# BMS.net
KiCad netlist of a schematic drawn in Altium Designer
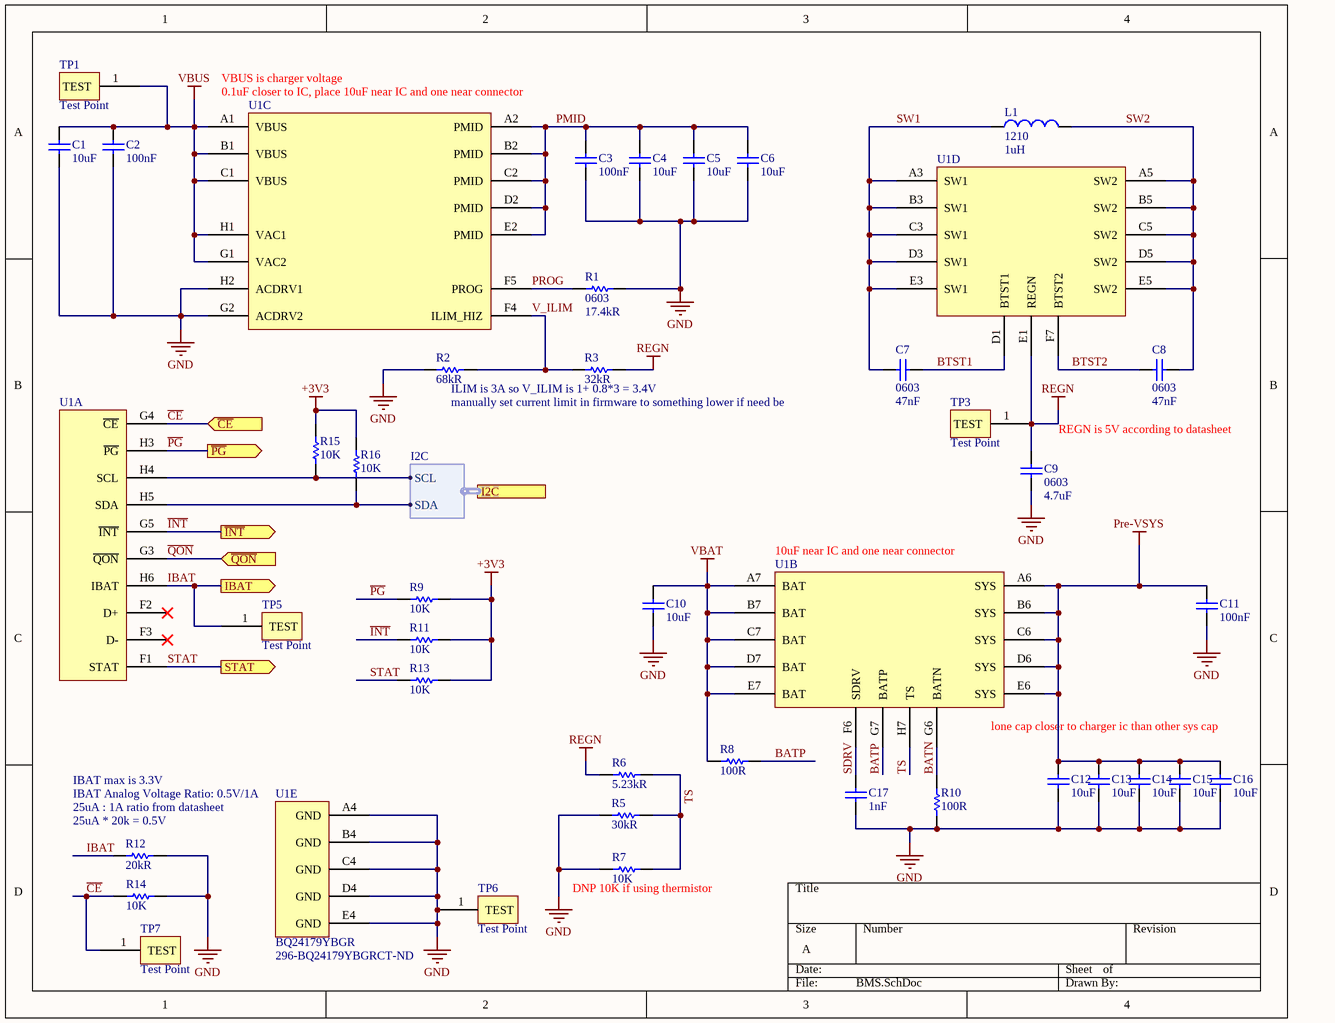
[diagram p0: BMS.SchDoc]

(export (version "E")
  (design (tool "Eeschema 10.0.6"))
  (components
    (comp (ref "C1")
      (value "Capacitor 0603")
      (footprint "C0603")
      (description "Multilayer Ceramic Capacitors (High dielectric type), 25V, 10 uF, ± 20 %, 0603, X5R, RoHS")
      (fields
        (field (name "MANUFACTURER") "Taiyo Yuden")
        (field (name "MANUFACTURER PART NUMBER") "TMK107BBJ106MA-T")
        (field (name "CAPACITANCE") "10uF")
      )
      (libsource (lib "Wally_BMS") (part "Capacitor 0603"))
    )
    (comp (ref "C2")
      (value "Capacitor 0402")
      (footprint "C0402")
      (description "CAP CER 0.1UF 25V X5R 0402 / High Value Multilayer Ceramic Capacitors (High dielectric type)")
      (fields
        (field (name "MANUFACTURER") "Taiyo Yuden")
        (field (name "MANUFACTURER PART NUMBER") "TMK105BJ104KV-F")
        (field (name "CAPACITANCE") "100nF")
      )
      (libsource (lib "Wally_BMS") (part "Capacitor 0402"))
    )
    (comp (ref "C3")
      (value "Capacitor 0402")
      (footprint "C0402")
      (description "CAP CER 0.1UF 25V X5R 0402 / High Value Multilayer Ceramic Capacitors (High dielectric type)")
      (fields
        (field (name "MANUFACTURER") "Taiyo Yuden")
        (field (name "MANUFACTURER PART NUMBER") "TMK105BJ104KV-F")
        (field (name "CAPACITANCE") "100nF")
      )
      (libsource (lib "Wally_BMS") (part "Capacitor 0402"))
    )
    (comp (ref "C4")
      (value "Capacitor 0603")
      (footprint "C0603")
      (description "Multilayer Ceramic Capacitors (High dielectric type), 25V, 10 uF, ± 20 %, 0603, X5R, RoHS")
      (fields
        (field (name "MANUFACTURER") "Taiyo Yuden")
        (field (name "MANUFACTURER PART NUMBER") "TMK107BBJ106MA-T")
        (field (name "CAPACITANCE") "10uF")
      )
      (libsource (lib "Wally_BMS") (part "Capacitor 0603"))
    )
    (comp (ref "C5")
      (value "Capacitor 0603")
      (footprint "C0603")
      (description "Multilayer Ceramic Capacitors (High dielectric type), 25V, 10 uF, ± 20 %, 0603, X5R, RoHS")
      (fields
        (field (name "MANUFACTURER") "Taiyo Yuden")
        (field (name "MANUFACTURER PART NUMBER") "TMK107BBJ106MA-T")
        (field (name "CAPACITANCE") "10uF")
      )
      (libsource (lib "Wally_BMS") (part "Capacitor 0603"))
    )
    (comp (ref "C6")
      (value "Capacitor 0603")
      (footprint "C0603")
      (description "Multilayer Ceramic Capacitors (High dielectric type), 25V, 10 uF, ± 20 %, 0603, X5R, RoHS")
      (fields
        (field (name "MANUFACTURER") "Taiyo Yuden")
        (field (name "MANUFACTURER PART NUMBER") "TMK107BBJ106MA-T")
        (field (name "CAPACITANCE") "10uF")
      )
      (libsource (lib "Wally_BMS") (part "Capacitor 0603"))
    )
    (comp (ref "C7")
      (value "Capacitor 0603")
      (footprint "C0603")
      (description "Cap Ceramic 0.047uF 50V X7R 10% SMD 0603 125°C Paper T/R")
      (fields
        (field (name "PACKAGE / CASE") "0603")
        (field (name "MANUFACTURER") "KEMET")
        (field (name "MANUFACTURER PART NUMBER") "C0603C473K5RAC7411")
        (field (name "CAPACITANCE") "47nF")
      )
      (libsource (lib "Wally_BMS") (part "Capacitor 0603"))
    )
    (comp (ref "C8")
      (value "Capacitor 0603")
      (footprint "C0603")
      (description "Cap Ceramic 0.047uF 50V X7R 10% SMD 0603 125°C Paper T/R")
      (fields
        (field (name "PACKAGE / CASE") "0603")
        (field (name "MANUFACTURER") "KEMET")
        (field (name "MANUFACTURER PART NUMBER") "C0603C473K5RAC7411")
        (field (name "CAPACITANCE") "47nF")
      )
      (libsource (lib "Wally_BMS") (part "Capacitor 0603"))
    )
    (comp (ref "C9")
      (value "Capacitor 0603")
      (footprint "C0603")
      (description "CAP CER 4.7UF 25V X5R 0603")
      (fields
        (field (name "PACKAGE / CASE") "0603")
        (field (name "MANUFACTURER") "TDK")
        (field (name "MANUFACTURER PART NUMBER") "C1608X5R1E475M080AC")
        (field (name "CAPACITANCE") "4.7uF")
      )
      (libsource (lib "Wally_BMS") (part "Capacitor 0603"))
    )
    (comp (ref "C10")
      (value "Capacitor 0603")
      (footprint "C0603")
      (description "Multilayer Ceramic Capacitors (High dielectric type), 25V, 10 uF, ± 20 %, 0603, X5R, RoHS")
      (fields
        (field (name "MANUFACTURER") "Taiyo Yuden")
        (field (name "MANUFACTURER PART NUMBER") "TMK107BBJ106MA-T")
        (field (name "CAPACITANCE") "10uF")
      )
      (libsource (lib "Wally_BMS") (part "Capacitor 0603"))
    )
    (comp (ref "C11")
      (value "Capacitor 0402")
      (footprint "C0402")
      (description "CAP CER 0.1UF 25V X5R 0402 / High Value Multilayer Ceramic Capacitors (High dielectric type)")
      (fields
        (field (name "MANUFACTURER") "Taiyo Yuden")
        (field (name "MANUFACTURER PART NUMBER") "TMK105BJ104KV-F")
        (field (name "CAPACITANCE") "100nF")
      )
      (libsource (lib "Wally_BMS") (part "Capacitor 0402"))
    )
    (comp (ref "C12")
      (value "Capacitor 0603")
      (footprint "C0603")
      (description "Multilayer Ceramic Capacitors (High dielectric type), 25V, 10 uF, ± 20 %, 0603, X5R, RoHS")
      (fields
        (field (name "MANUFACTURER") "Taiyo Yuden")
        (field (name "MANUFACTURER PART NUMBER") "TMK107BBJ106MA-T")
        (field (name "CAPACITANCE") "10uF")
      )
      (libsource (lib "Wally_BMS") (part "Capacitor 0603"))
    )
    (comp (ref "C13")
      (value "Capacitor 0603")
      (footprint "C0603")
      (description "Multilayer Ceramic Capacitors (High dielectric type), 25V, 10 uF, ± 20 %, 0603, X5R, RoHS")
      (fields
        (field (name "MANUFACTURER") "Taiyo Yuden")
        (field (name "MANUFACTURER PART NUMBER") "TMK107BBJ106MA-T")
        (field (name "CAPACITANCE") "10uF")
      )
      (libsource (lib "Wally_BMS") (part "Capacitor 0603"))
    )
    (comp (ref "C14")
      (value "Capacitor 0603")
      (footprint "C0603")
      (description "Multilayer Ceramic Capacitors (High dielectric type), 25V, 10 uF, ± 20 %, 0603, X5R, RoHS")
      (fields
        (field (name "MANUFACTURER") "Taiyo Yuden")
        (field (name "MANUFACTURER PART NUMBER") "TMK107BBJ106MA-T")
        (field (name "CAPACITANCE") "10uF")
      )
      (libsource (lib "Wally_BMS") (part "Capacitor 0603"))
    )
    (comp (ref "C15")
      (value "Capacitor 0603")
      (footprint "C0603")
      (description "Multilayer Ceramic Capacitors (High dielectric type), 25V, 10 uF, ± 20 %, 0603, X5R, RoHS")
      (fields
        (field (name "MANUFACTURER") "Taiyo Yuden")
        (field (name "MANUFACTURER PART NUMBER") "TMK107BBJ106MA-T")
        (field (name "CAPACITANCE") "10uF")
      )
      (libsource (lib "Wally_BMS") (part "Capacitor 0603"))
    )
    (comp (ref "C16")
      (value "Capacitor 0603")
      (footprint "C0603")
      (description "Multilayer Ceramic Capacitors (High dielectric type), 25V, 10 uF, ± 20 %, 0603, X5R, RoHS")
      (fields
        (field (name "MANUFACTURER") "Taiyo Yuden")
        (field (name "MANUFACTURER PART NUMBER") "TMK107BBJ106MA-T")
        (field (name "CAPACITANCE") "10uF")
      )
      (libsource (lib "Wally_BMS") (part "Capacitor 0603"))
    )
    (comp (ref "C17")
      (value "478-1215-1-ND")
      (footprint "C0603")
      (description "CAP CER 1000PF 50V X7R 0603")
      (fields (field (name "TOLERANCE") "±20%") (field (name "CAPACITANCE") "1nF"))
      (libsource (lib "Capacitors") (part "06035C102KAT2A"))
    )
    (comp (ref "L1")
      (value "Inductor 1210")
      (footprint "ind1210")
      (description "Inductor Power Shielded Wirewound 1uH 20% 1MHz Metal 4.1A 0.022Ohm DCR 1210 Automotive T/R")
      (fields
        (field (name "PACKAGE / CASE") "1210")
        (field (name "MANUFACTURER") "Murata")
        (field (name "MANUFACTURER PART NUMBER") "DFE322520FD-1R0M=P2")
        (field (name "INDUCTANCE") "1uH")
      )
      (libsource (lib "Wally_BMS") (part "Inductor 1210"))
    )
    (comp (ref "R1")
      (value "Resistor 0603")
      (footprint "RES0603")
      (description "Res Thick Film 0603 17.4K Ohm 1% 0.1W(1/10W) ±100ppm/°C Pad SMD Automotive T/R")
      (fields
        (field (name "PACKAGE / CASE") "0603")
        (field (name "MANUFACTURER") "Stackpole Electronics")
        (field (name "MANUFACTURER PART NUMBER") "RMCF0603FT17K4")
        (field (name "RESISTANCE") "17.4kR")
      )
      (libsource (lib "Wally_BMS") (part "Resistor 0603"))
    )
    (comp (ref "R2")
      (value "Resistor 0402")
      (footprint "RES0402")
      (description "Res Thin Film 0402 68K Ohm 0.1% 0.063W ±25ppm/°C Molded SMD Punched Carrier T/R")
      (fields
        (field (name "MANUFACTURER") "Panasonic")
        (field (name "MANUFACTURER PART NUMBER") "ERA-2AEB683X")
        (field (name "RESISTANCE") "68kR")
      )
      (libsource (lib "Wally_BMS") (part "Resistor 0402"))
    )
    (comp (ref "R3")
      (value "Resistor 0402")
      (footprint "RES0402")
      (description "Res, 32K, 1%, 0.063W, 0402 Rohs Compliant: Yes")
      (fields
        (field (name "MANUFACTURER") "KOA Speer")
        (field (name "MANUFACTURER PART NUMBER") "RN73H1ETTP3202F50")
        (field (name "RESISTANCE") "32kR")
      )
      (libsource (lib "Wally_BMS") (part "Resistor 0402"))
    )
    (comp (ref "R5")
      (value "Resistor 0402")
      (footprint "RES0402")
      (description "Res Thick Film 0402 30K Ohm 5% 0.063W(1/16W) ±100ppm/C Pad SMD Automotive T/R")
      (fields
        (field (name "MANUFACTURER") "Stackpole Electronics")
        (field (name "MANUFACTURER PART NUMBER") "RMCF0402JT30K0")
        (field (name "RESISTANCE") "30kR")
      )
      (libsource (lib "Wally_BMS") (part "Resistor 0402"))
    )
    (comp (ref "R6")
      (value "Resistor 0402")
      (footprint "RES0402")
      (description "Res Thick Film 0402 5.23K Ohm 1% 0.063W ±100ppm/°C Molded SMD Paper T/R")
      (fields
        (field (name "MANUFACTURER") "Stackpole Electronics")
        (field (name "MANUFACTURER PART NUMBER") "RMCF0402FT5K23")
        (field (name "RESISTANCE") "5.23kR")
      )
      (libsource (lib "Wally_BMS") (part "Resistor 0402"))
    )
    (comp (ref "R7")
      (value "ERJ-PB3B1002V")
      (footprint "RES0603")
      (description "RES SMD 10K OHM 5% 1/4W 0603")
      (fields (field (name "TOLERANCE") "±1%") (field (name "RESISTANCE (OHMS)") "10K"))
      (libsource (lib "Resistors") (part "ERJ-PB3B1002V"))
    )
    (comp (ref "R8")
      (value "Resistor 0603")
      (footprint "RES0603")
      (description "Res Thick Film 0603 100 Ohm 1% 0.1W(1/10W) ±100ppm/°C Pad SMD Automotive T/R")
      (fields
        (field (name "MANUFACTURER") "Stackpole Electronics")
        (field (name "MANUFACTURER PART NUMBER") "RMCF0603FT100R")
        (field (name "RESISTANCE") "100R")
      )
      (libsource (lib "Wally_BMS") (part "Resistor 0603"))
    )
    (comp (ref "R9")
      (value "ERJ-PB3B1002V")
      (footprint "RES0603")
      (description "RES SMD 10K OHM 5% 1/4W 0603")
      (fields (field (name "TOLERANCE") "±1%") (field (name "RESISTANCE (OHMS)") "10K"))
      (libsource (lib "Resistors") (part "ERJ-PB3B1002V"))
    )
    (comp (ref "R10")
      (value "Resistor 0603")
      (footprint "RES0603")
      (description "Res Thick Film 0603 100 Ohm 1% 0.1W(1/10W) ±100ppm/°C Pad SMD Automotive T/R")
      (fields
        (field (name "MANUFACTURER") "Stackpole Electronics")
        (field (name "MANUFACTURER PART NUMBER") "RMCF0603FT100R")
        (field (name "RESISTANCE") "100R")
      )
      (libsource (lib "Wally_BMS") (part "Resistor 0603"))
    )
    (comp (ref "R11")
      (value "ERJ-PB3B1002V")
      (footprint "RES0603")
      (description "RES SMD 10K OHM 5% 1/4W 0603")
      (fields (field (name "TOLERANCE") "±1%") (field (name "RESISTANCE (OHMS)") "10K"))
      (libsource (lib "Resistors") (part "ERJ-PB3B1002V"))
    )
    (comp (ref "R12")
      (value "Resistor 0603")
      (footprint "RES0603")
      (description "Res Thick Film 0603 20K Ohm 1% 0.1W(1/10W) ±100ppm/C Pad SMD Automotive T/R")
      (fields
        (field (name "MANUFACTURER") "Stackpole Electronics")
        (field (name "MANUFACTURER PART NUMBER") "RMCF0603FT20K0")
        (field (name "RESISTANCE") "20kR")
      )
      (libsource (lib "Wally_BMS") (part "Resistor 0603"))
    )
    (comp (ref "R13")
      (value "ERJ-PB3B1002V")
      (footprint "RES0603")
      (description "RES SMD 10K OHM 5% 1/4W 0603")
      (fields (field (name "TOLERANCE") "±1%") (field (name "RESISTANCE (OHMS)") "10K"))
      (libsource (lib "Resistors") (part "ERJ-PB3B1002V"))
    )
    (comp (ref "R14")
      (value "ERJ-PB3B1002V")
      (footprint "RES0603")
      (description "RES SMD 10K OHM 5% 1/4W 0603")
      (fields (field (name "TOLERANCE") "±1%") (field (name "RESISTANCE (OHMS)") "10K"))
      (libsource (lib "Resistors") (part "ERJ-PB3B1002V"))
    )
    (comp (ref "R15")
      (value "ERJ-PB3B1002V")
      (footprint "RES0603")
      (description "RES SMD 10K OHM 5% 1/4W 0603")
      (fields (field (name "TOLERANCE") "±1%") (field (name "RESISTANCE (OHMS)") "10K"))
      (libsource (lib "Resistors") (part "ERJ-PB3B1002V"))
    )
    (comp (ref "R16")
      (value "ERJ-PB3B1002V")
      (footprint "RES0603")
      (description "RES SMD 10K OHM 5% 1/4W 0603")
      (fields (field (name "TOLERANCE") "±1%") (field (name "RESISTANCE (OHMS)") "10K"))
      (libsource (lib "Resistors") (part "ERJ-PB3B1002V"))
    )
    (comp (ref "TP1")
      (value "Test Point")
      (footprint "TEST POINT")
      (libsource (lib "") (part "Test Point_1"))
    )
    (comp (ref "TP3")
      (value "Test Point")
      (footprint "TEST POINT")
      (libsource (lib "") (part "Test Point_1"))
    )
    (comp (ref "TP5")
      (value "Test Point")
      (footprint "TEST POINT")
      (libsource (lib "Wally_BMS") (part "Test Point"))
    )
    (comp (ref "TP6")
      (value "Test Point")
      (footprint "TEST POINT")
      (libsource (lib "Wally_BMS") (part "Test Point"))
    )
    (comp (ref "TP7")
      (value "Test Point")
      (footprint "TEST POINT")
      (libsource (lib "Wally_BMS") (part "Test Point"))
    )
    (comp (ref "U1")
      (value "BQ24179YBGR")
      (footprint "BGA_79YBGR_TEX")
      (description "INTEGRATED, NVDC, 5-A 1-CELL TO")
      (fields
        (field (name "MANUFACTURER") "Texas Instruments")
        (field (name "SUPPLIER PART NUMBER 1") "296-BQ24179YBGRCT-ND")
      )
      (libsource (lib "Wally_BMS") (part "BQ24179YBGR"))
    )
  )
  (nets
    (net (code "2") (name "+3V3") (class "Default")
      (node (ref "R11") (pin "1") (pinfunction "1_1") (pintype "passive"))
      (node (ref "R13") (pin "1") (pinfunction "1_1") (pintype "passive"))
      (node (ref "R15") (pin "1") (pinfunction "1_1") (pintype "passive"))
      (node (ref "R16") (pin "1") (pinfunction "1_1") (pintype "passive"))
      (node (ref "R9") (pin "1") (pinfunction "1_1") (pintype "passive"))
    )
    (net (code "3") (name "/BATN") (class "Default")
      (node (ref "R10") (pin "2") (pinfunction "2_2") (pintype "passive"))
      (node (ref "U1") (pin "G6") (pinfunction "BATN_G6") (pintype "passive"))
    )
    (net (code "4") (name "/BATP") (class "Default")
      (node (ref "R8") (pin "1") (pinfunction "1_1") (pintype "passive"))
      (node (ref "U1") (pin "G7") (pinfunction "BATP_G7") (pintype "passive"))
    )
    (net (code "5") (name "/BTST1") (class "Default")
      (node (ref "C7") (pin "2") (pinfunction "2_2") (pintype "passive"))
      (node (ref "U1") (pin "D1") (pinfunction "BTST1_D1") (pintype "passive"))
    )
    (net (code "6") (name "/BTST2") (class "Default")
      (node (ref "C8") (pin "1") (pinfunction "1_1") (pintype "passive"))
      (node (ref "U1") (pin "F7") (pinfunction "BTST2_F7") (pintype "passive"))
    )
    (net (code "7") (name "/IBAT") (class "Default")
      (node (ref "R12") (pin "1") (pinfunction "1_1") (pintype "passive"))
      (node (ref "TP5") (pin "1") (pinfunction "TEST_1") (pintype "passive"))
      (node (ref "U1") (pin "H6") (pinfunction "IBAT_H6") (pintype "passive"))
    )
    (net (code "8") (name "/PMID") (class "Default")
      (node (ref "C3") (pin "2") (pinfunction "2_2") (pintype "passive"))
      (node (ref "C4") (pin "2") (pinfunction "2_2") (pintype "passive"))
      (node (ref "C5") (pin "2") (pinfunction "2_2") (pintype "passive"))
      (node (ref "C6") (pin "2") (pinfunction "2_2") (pintype "passive"))
      (node (ref "U1") (pin "A2") (pinfunction "PMID_A2") (pintype "passive"))
      (node (ref "U1") (pin "B2") (pinfunction "PMID_B2") (pintype "passive"))
      (node (ref "U1") (pin "C2") (pinfunction "PMID_C2") (pintype "passive"))
      (node (ref "U1") (pin "D2") (pinfunction "PMID_D2") (pintype "passive"))
      (node (ref "U1") (pin "E2") (pinfunction "PMID_E2") (pintype "passive"))
    )
    (net (code "9") (name "/PROG") (class "Default")
      (node (ref "R1") (pin "2") (pinfunction "2_2") (pintype "passive"))
      (node (ref "U1") (pin "F5") (pinfunction "PROG_F5") (pintype "passive"))
    )
    (net (code "10") (name "/SDRV") (class "Default")
      (node (ref "C17") (pin "2") (pinfunction "2_2") (pintype "passive"))
      (node (ref "U1") (pin "F6") (pinfunction "SDRV_F6") (pintype "passive"))
    )
    (net (code "11") (name "/STAT") (class "Default")
      (node (ref "R13") (pin "2") (pinfunction "2_2") (pintype "passive"))
      (node (ref "U1") (pin "F1") (pinfunction "STAT_F1") (pintype "passive"))
    )
    (net (code "12") (name "/SW1") (class "Default")
      (node (ref "C7") (pin "1") (pinfunction "1_1") (pintype "passive"))
      (node (ref "L1") (pin "1") (pinfunction "1_1") (pintype "passive"))
      (node (ref "U1") (pin "A3") (pinfunction "SW1_A3") (pintype "passive"))
      (node (ref "U1") (pin "B3") (pinfunction "SW1_B3") (pintype "passive"))
      (node (ref "U1") (pin "C3") (pinfunction "SW1_C3") (pintype "passive"))
      (node (ref "U1") (pin "D3") (pinfunction "SW1_D3") (pintype "passive"))
      (node (ref "U1") (pin "E3") (pinfunction "SW1_E3") (pintype "passive"))
    )
    (net (code "13") (name "/SW2") (class "Default")
      (node (ref "C8") (pin "2") (pinfunction "2_2") (pintype "passive"))
      (node (ref "L1") (pin "2") (pinfunction "2_2") (pintype "passive"))
      (node (ref "U1") (pin "A5") (pinfunction "SW2_A5") (pintype "passive"))
      (node (ref "U1") (pin "B5") (pinfunction "SW2_B5") (pintype "passive"))
      (node (ref "U1") (pin "C5") (pinfunction "SW2_C5") (pintype "passive"))
      (node (ref "U1") (pin "D5") (pinfunction "SW2_D5") (pintype "passive"))
      (node (ref "U1") (pin "E5") (pinfunction "SW2_E5") (pintype "passive"))
    )
    (net (code "14") (name "/TS") (class "Default")
      (node (ref "R5") (pin "2") (pinfunction "2_2") (pintype "passive"))
      (node (ref "R6") (pin "1") (pinfunction "1_1") (pintype "passive"))
      (node (ref "R7") (pin "1") (pinfunction "1_1") (pintype "passive"))
      (node (ref "U1") (pin "H7") (pinfunction "TS_H7") (pintype "passive"))
    )
    (net (code "15") (name "/V_ILIM") (class "Default")
      (node (ref "R2") (pin "2") (pinfunction "2_2") (pintype "passive"))
      (node (ref "R3") (pin "1") (pinfunction "1_1") (pintype "passive"))
      (node (ref "U1") (pin "F4") (pinfunction "ILIM_HIZ_F4") (pintype "passive"))
    )
    (net (code "17") (name "/~{CE}") (class "Default")
      (node (ref "R14") (pin "2") (pinfunction "2_2") (pintype "passive"))
      (node (ref "TP7") (pin "1") (pinfunction "TEST_1") (pintype "passive"))
      (node (ref "U1") (pin "G4") (pinfunction "~{CE}_G4") (pintype "passive"))
    )
    (net (code "18") (name "/~{INT}") (class "Default")
      (node (ref "R11") (pin "2") (pinfunction "2_2") (pintype "passive"))
      (node (ref "U1") (pin "G5") (pinfunction "~{INT}_G5") (pintype "passive"))
    )
    (net (code "19") (name "/~{PG}") (class "Default")
      (node (ref "R9") (pin "2") (pinfunction "2_2") (pintype "passive"))
      (node (ref "U1") (pin "H3") (pinfunction "~{PG}_H3") (pintype "passive"))
    )
    (net (code "20") (name "/~{QON}") (class "Default")
      (node (ref "U1") (pin "G3") (pinfunction "~{QON}_G3") (pintype "passive"))
    )
    (net (code "21") (name "GND") (class "Default")
      (node (ref "C1") (pin "1") (pinfunction "1_1") (pintype "passive"))
      (node (ref "C10") (pin "1") (pinfunction "1_1") (pintype "passive"))
      (node (ref "C11") (pin "1") (pinfunction "1_1") (pintype "passive"))
      (node (ref "C12") (pin "1") (pinfunction "1_1") (pintype "passive"))
      (node (ref "C13") (pin "1") (pinfunction "1_1") (pintype "passive"))
      (node (ref "C14") (pin "1") (pinfunction "1_1") (pintype "passive"))
      (node (ref "C15") (pin "1") (pinfunction "1_1") (pintype "passive"))
      (node (ref "C16") (pin "1") (pinfunction "1_1") (pintype "passive"))
      (node (ref "C17") (pin "1") (pinfunction "1_1") (pintype "passive"))
      (node (ref "C2") (pin "1") (pinfunction "1_1") (pintype "passive"))
      (node (ref "C3") (pin "1") (pinfunction "1_1") (pintype "passive"))
      (node (ref "C4") (pin "1") (pinfunction "1_1") (pintype "passive"))
      (node (ref "C5") (pin "1") (pinfunction "1_1") (pintype "passive"))
      (node (ref "C6") (pin "1") (pinfunction "1_1") (pintype "passive"))
      (node (ref "C9") (pin "1") (pinfunction "1_1") (pintype "passive"))
      (node (ref "R1") (pin "1") (pinfunction "1_1") (pintype "passive"))
      (node (ref "R10") (pin "1") (pinfunction "1_1") (pintype "passive"))
      (node (ref "R12") (pin "2") (pinfunction "2_2") (pintype "passive"))
      (node (ref "R14") (pin "1") (pinfunction "1_1") (pintype "passive"))
      (node (ref "R2") (pin "1") (pinfunction "1_1") (pintype "passive"))
      (node (ref "R5") (pin "1") (pinfunction "1_1") (pintype "passive"))
      (node (ref "R7") (pin "2") (pinfunction "2_2") (pintype "passive"))
      (node (ref "TP6") (pin "1") (pinfunction "TEST_1") (pintype "passive"))
      (node (ref "U1") (pin "A4") (pinfunction "GND_A4") (pintype "passive"))
      (node (ref "U1") (pin "B4") (pinfunction "GND_B4") (pintype "passive"))
      (node (ref "U1") (pin "C4") (pinfunction "GND_C4") (pintype "passive"))
      (node (ref "U1") (pin "D4") (pinfunction "GND_D4") (pintype "passive"))
      (node (ref "U1") (pin "E4") (pinfunction "GND_E4") (pintype "passive"))
      (node (ref "U1") (pin "G2") (pinfunction "ACDRV2_G2") (pintype "passive"))
      (node (ref "U1") (pin "H2") (pinfunction "ACDRV1_H2") (pintype "passive"))
    )
    (net (code "22") (name "Net-(U1A-SCL)") (class "Default")
      (node (ref "R15") (pin "2") (pinfunction "2_2") (pintype "passive"))
      (node (ref "U1") (pin "H4") (pinfunction "SCL_H4") (pintype "passive"))
    )
    (net (code "23") (name "Net-(U1A-SDA)") (class "Default")
      (node (ref "R16") (pin "2") (pinfunction "2_2") (pintype "passive"))
      (node (ref "U1") (pin "H5") (pinfunction "SDA_H5") (pintype "passive"))
    )
    (net (code "24") (name "Pre-VSYS") (class "Default")
      (node (ref "C11") (pin "2") (pinfunction "2_2") (pintype "passive"))
      (node (ref "C12") (pin "2") (pinfunction "2_2") (pintype "passive"))
      (node (ref "C13") (pin "2") (pinfunction "2_2") (pintype "passive"))
      (node (ref "C14") (pin "2") (pinfunction "2_2") (pintype "passive"))
      (node (ref "C15") (pin "2") (pinfunction "2_2") (pintype "passive"))
      (node (ref "C16") (pin "2") (pinfunction "2_2") (pintype "passive"))
      (node (ref "U1") (pin "A6") (pinfunction "SYS_A6") (pintype "passive"))
      (node (ref "U1") (pin "B6") (pinfunction "SYS_B6") (pintype "passive"))
      (node (ref "U1") (pin "C6") (pinfunction "SYS_C6") (pintype "passive"))
      (node (ref "U1") (pin "D6") (pinfunction "SYS_D6") (pintype "passive"))
      (node (ref "U1") (pin "E6") (pinfunction "SYS_E6") (pintype "passive"))
    )
    (net (code "25") (name "REGN") (class "Default")
      (node (ref "C9") (pin "2") (pinfunction "2_2") (pintype "passive"))
      (node (ref "R3") (pin "2") (pinfunction "2_2") (pintype "passive"))
      (node (ref "R6") (pin "2") (pinfunction "2_2") (pintype "passive"))
      (node (ref "TP3") (pin "1") (pinfunction "TEST_1") (pintype "passive"))
      (node (ref "U1") (pin "E1") (pinfunction "REGN_E1") (pintype "passive"))
    )
    (net (code "26") (name "VBAT") (class "Default")
      (node (ref "C10") (pin "2") (pinfunction "2_2") (pintype "passive"))
      (node (ref "R8") (pin "2") (pinfunction "2_2") (pintype "passive"))
      (node (ref "U1") (pin "A7") (pinfunction "BAT_A7") (pintype "passive"))
      (node (ref "U1") (pin "B7") (pinfunction "BAT_B7") (pintype "passive"))
      (node (ref "U1") (pin "C7") (pinfunction "BAT_C7") (pintype "passive"))
      (node (ref "U1") (pin "D7") (pinfunction "BAT_D7") (pintype "passive"))
      (node (ref "U1") (pin "E7") (pinfunction "BAT_E7") (pintype "passive"))
    )
    (net (code "27") (name "VBUS") (class "Default")
      (node (ref "C1") (pin "2") (pinfunction "2_2") (pintype "passive"))
      (node (ref "C2") (pin "2") (pinfunction "2_2") (pintype "passive"))
      (node (ref "TP1") (pin "1") (pinfunction "TEST_1") (pintype "passive"))
      (node (ref "U1") (pin "A1") (pinfunction "VBUS_A1") (pintype "passive"))
      (node (ref "U1") (pin "B1") (pinfunction "VBUS_B1") (pintype "passive"))
      (node (ref "U1") (pin "C1") (pinfunction "VBUS_C1") (pintype "passive"))
      (node (ref "U1") (pin "G1") (pinfunction "VAC2_G1") (pintype "passive"))
      (node (ref "U1") (pin "H1") (pinfunction "VAC1_H1") (pintype "passive"))
    )
    (net (code "28") (name "unconnected-(U1A-D+-PadF2)") (class "Default")
      (node (ref "U1") (pin "F2") (pinfunction "D+_F2") (pintype "passive+no_connect"))
    )
    (net (code "29") (name "unconnected-(U1A-D--PadF3)") (class "Default")
      (node (ref "U1") (pin "F3") (pinfunction "D-_F3") (pintype "passive+no_connect"))
    )
  )
)
